# controller.net
KiCad netlist of a schematic drawn in EAGLE
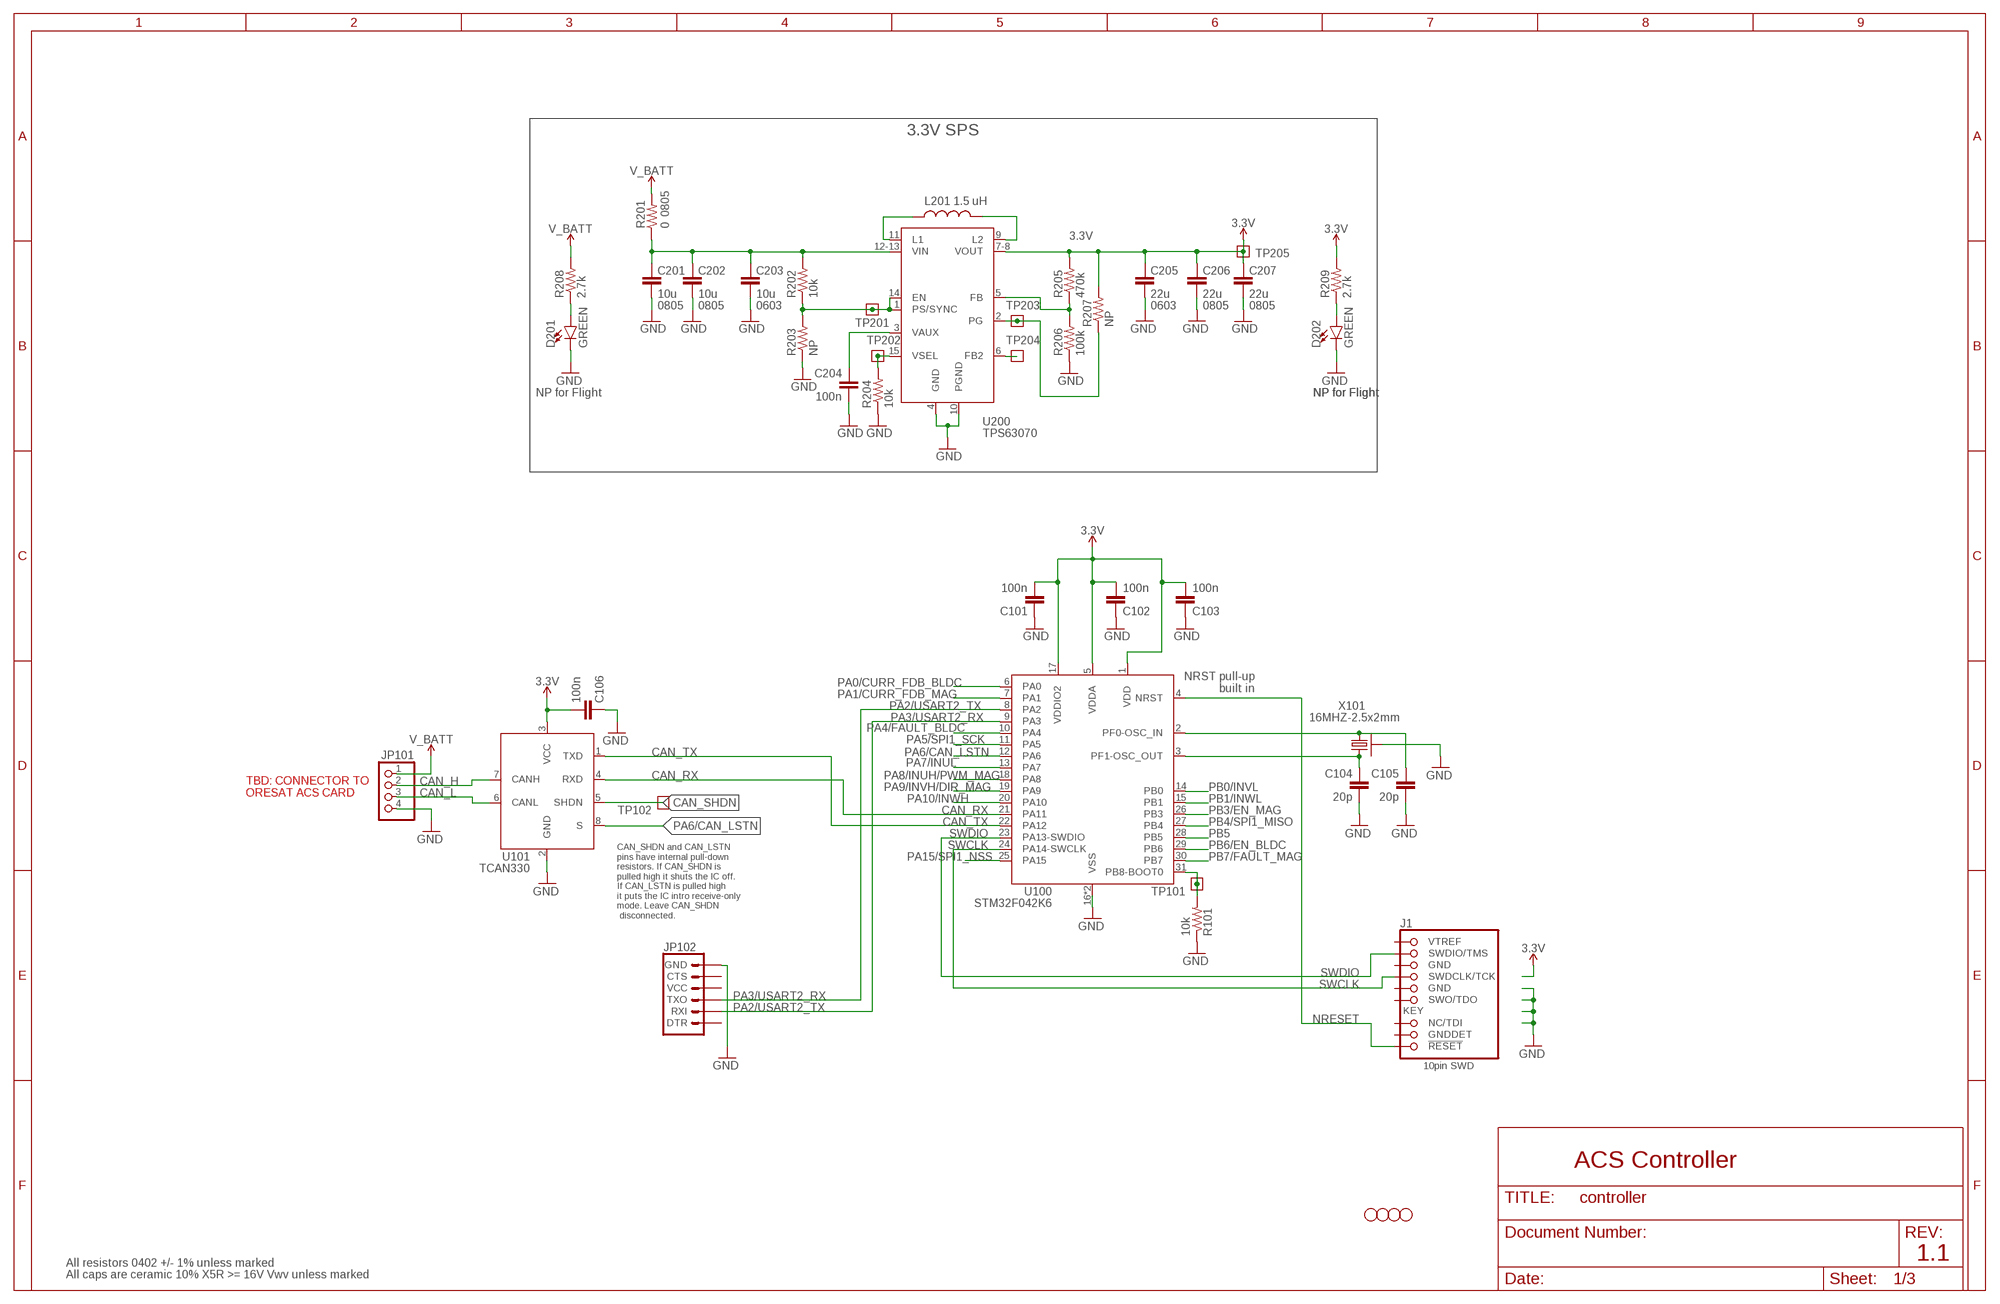
[diagram p0: schematic, sheet 1]
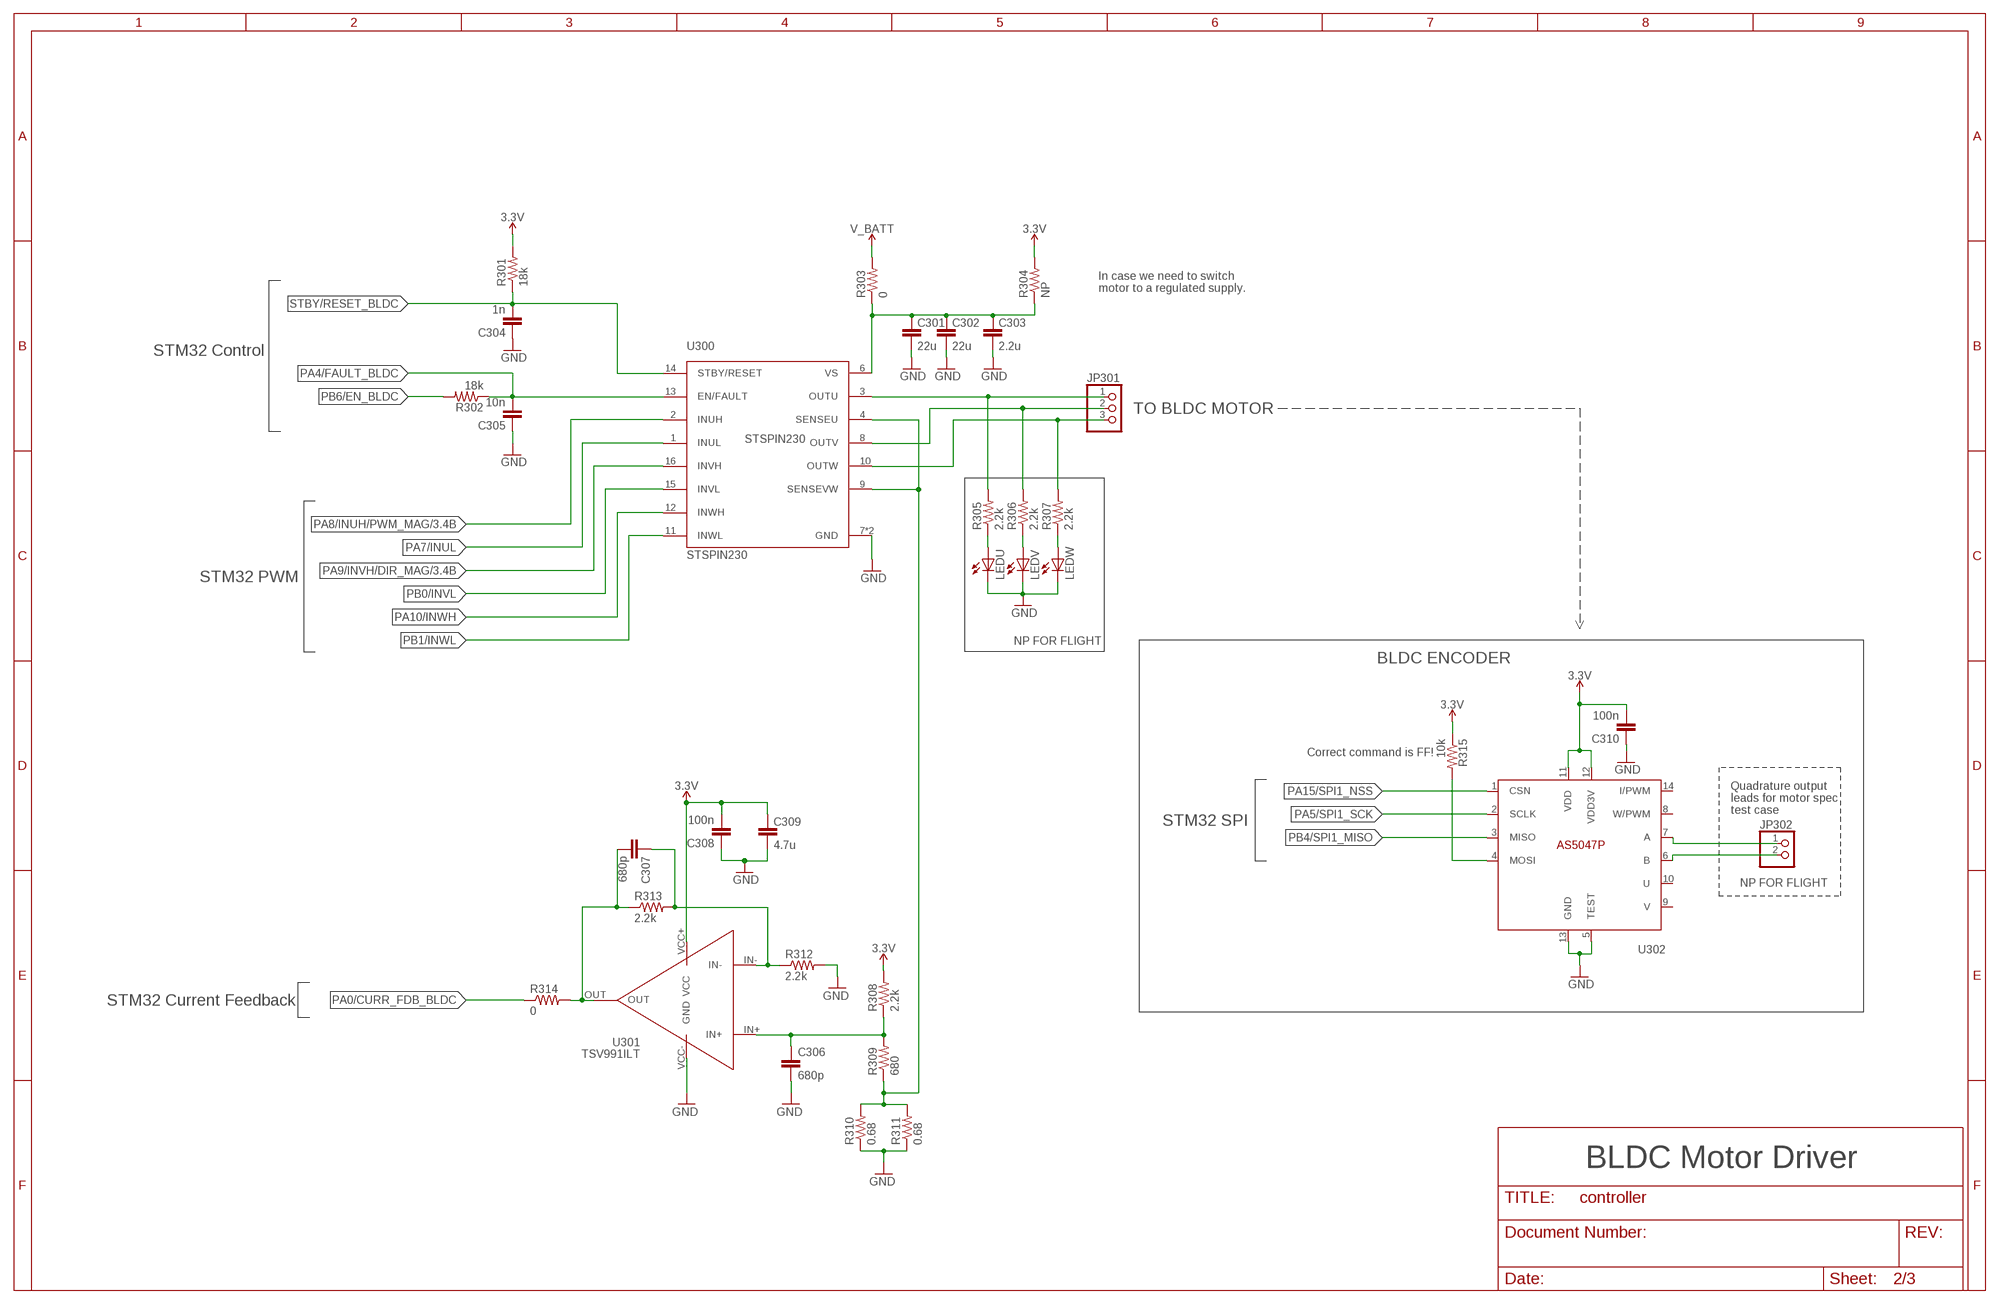
[diagram p1: schematic, sheet 2]
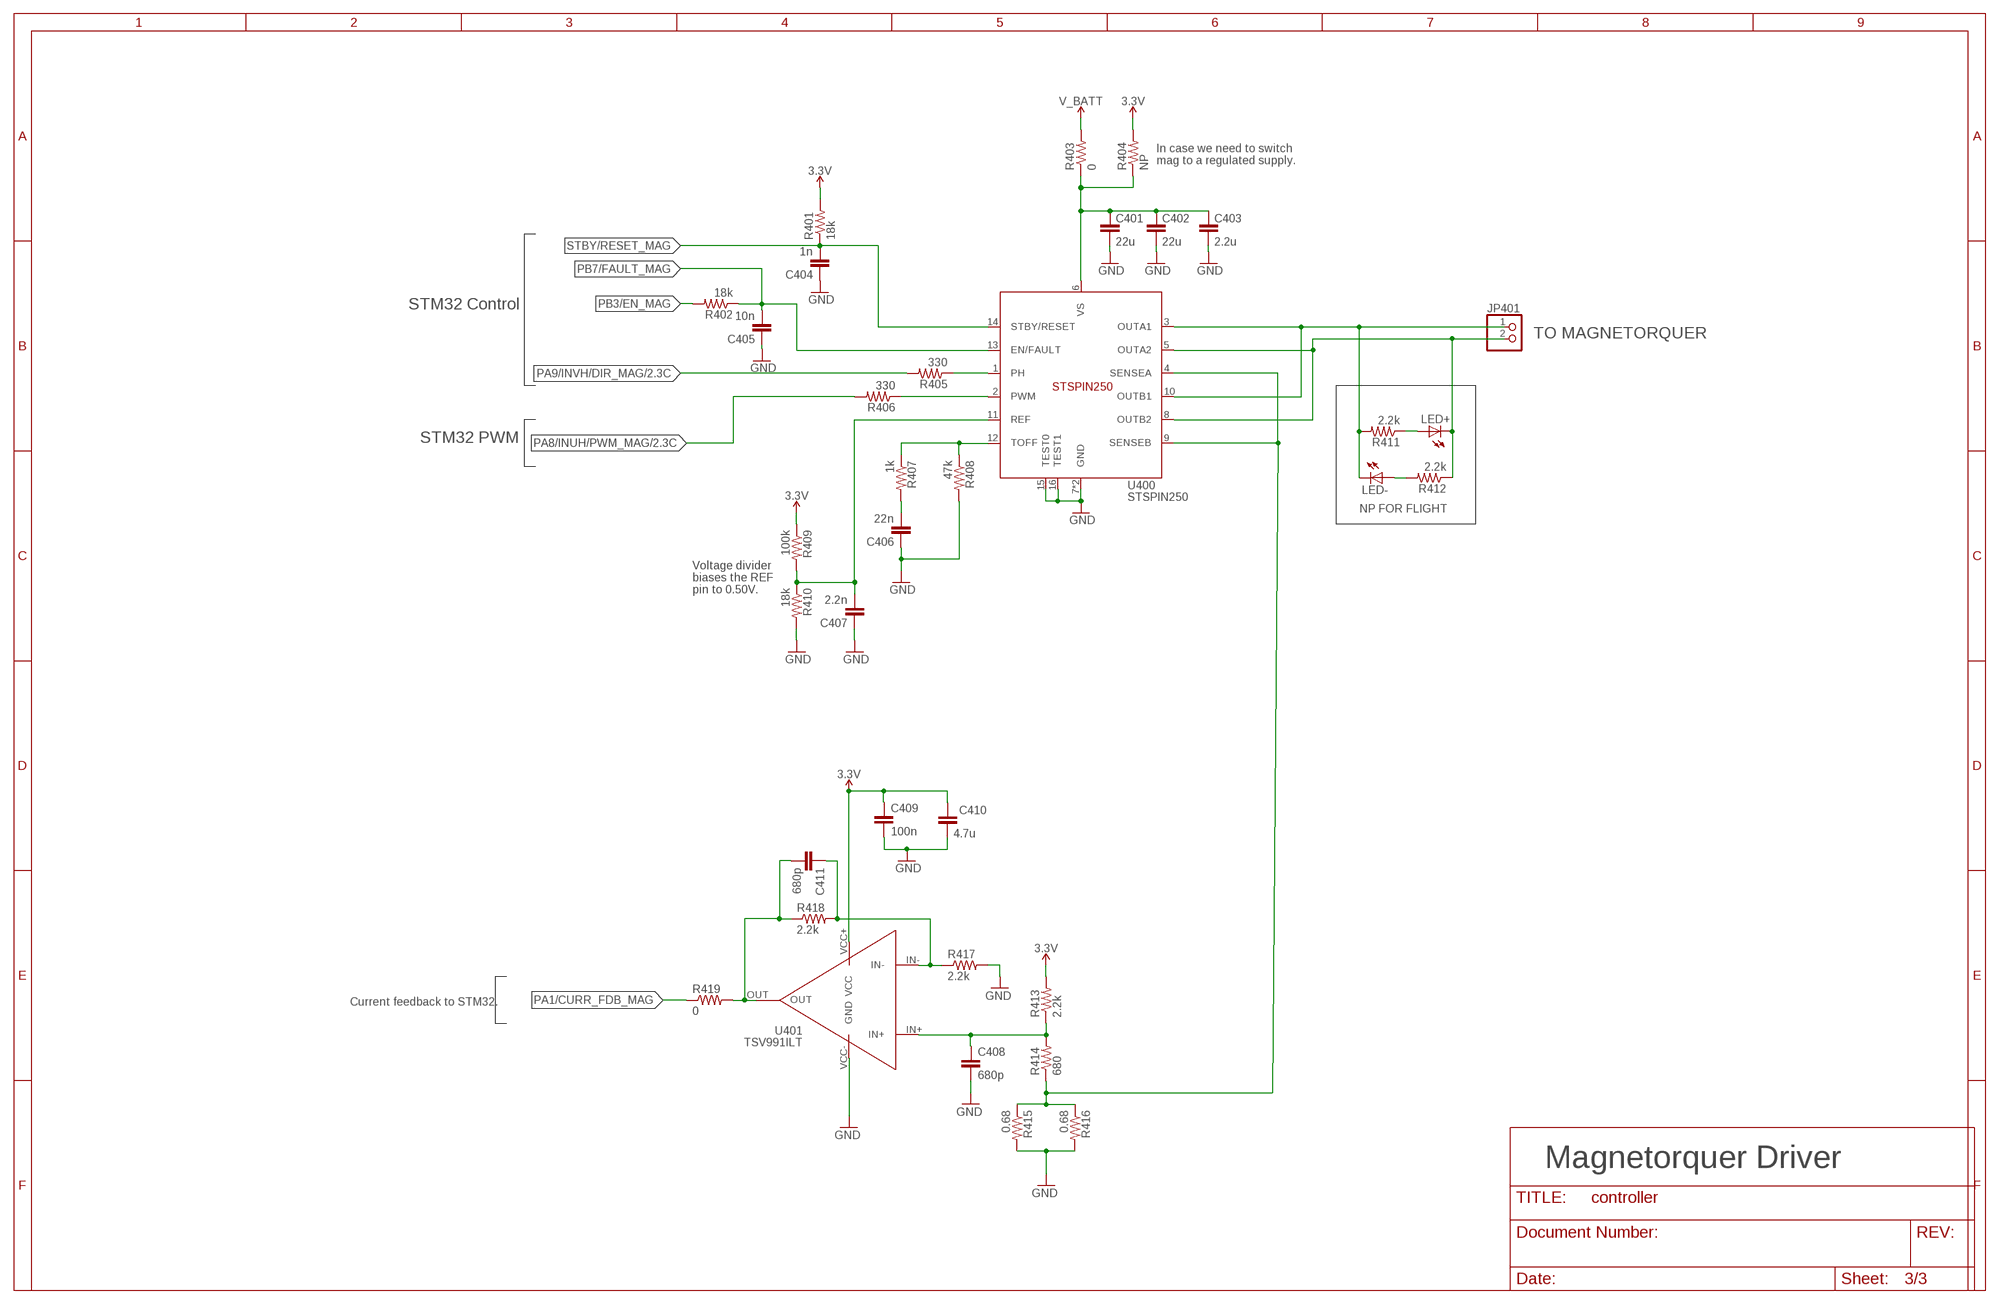
[diagram p2: schematic, sheet 3]

(export (version "E")
  (design (tool "Eeschema 10.0.6"))
  (components
    (comp (ref "C101")
      (value "100n")
      (footprint "eagle-import:.0402-B-NOSILK")
      (fields (field (name "MFR") "Samsung") (field (name "MPN") "CL05B104KO5NNNC"))
      (libsource (lib "eagle-import") (part "rcl_custom_C-EU0402-B-NOSILK"))
    )
    (comp (ref "C102")
      (value "100n")
      (footprint "eagle-import:.0402-B-NOSILK")
      (fields (field (name "MFR") "Samsung") (field (name "MPN") "CL05B104KO5NNNC"))
      (libsource (lib "eagle-import") (part "rcl_custom_C-EU0402-B-NOSILK"))
    )
    (comp (ref "C103")
      (value "100n")
      (footprint "eagle-import:.0402-B-NOSILK")
      (fields (field (name "MFR") "Samsung") (field (name "MPN") "CL05B104KO5NNNC"))
      (libsource (lib "eagle-import") (part "rcl_custom_C-EU0402-B-NOSILK"))
    )
    (comp (ref "C104")
      (value "20p")
      (footprint "eagle-import:.0402-B-NOSILK")
      (fields (field (name "MFR") "Samsung") (field (name "MPN") "CL05C200JB51PNC"))
      (libsource (lib "eagle-import") (part "rcl_custom_C-EU0402-B-NOSILK"))
    )
    (comp (ref "C105")
      (value "20p")
      (footprint "eagle-import:.0402-B-NOSILK")
      (fields (field (name "MFR") "Samsung") (field (name "MPN") "CL05C200JB51PNC"))
      (libsource (lib "eagle-import") (part "rcl_custom_C-EU0402-B-NOSILK"))
    )
    (comp (ref "C106")
      (value "100n")
      (footprint "eagle-import:.0402-B-NOSILK")
      (fields (field (name "MFR") "Samsung") (field (name "MPN") "CL05B104KO5NNNC"))
      (libsource (lib "eagle-import") (part "rcl_custom_C-EU0402-B-NOSILK"))
    )
    (comp (ref "C201")
      (value "10u")
      (footprint "eagle-import:.0805-B-NOSILK")
      (libsource (lib "eagle-import") (part "C-EU0805-B-NOSILK"))
    )
    (comp (ref "C202")
      (value "10u")
      (footprint "eagle-import:.0805-B-NOSILK")
      (libsource (lib "eagle-import") (part "C-EU0805-B-NOSILK"))
    )
    (comp (ref "C203")
      (value "10u")
      (footprint "eagle-import:.0603-B-NOSILK")
      (fields (field (name "MFR") "Samsung") (field (name "MPN") "CL05B104KO5NNNC"))
      (libsource (lib "eagle-import") (part "C-EU0603-B-NOSILK"))
    )
    (comp (ref "C204")
      (value "100n")
      (footprint "eagle-import:.0402-B-NOSILK")
      (fields (field (name "MFR") "Samsung") (field (name "MPN") "CL05B104KO5NNNC"))
      (libsource (lib "eagle-import") (part "rcl_custom_C-EU0402-B-NOSILK"))
    )
    (comp (ref "C205")
      (value "22u")
      (footprint "eagle-import:.0603-B-NOSILK")
      (fields (field (name "MFR") "Samsung") (field (name "MPN") "CL05B104KO5NNNC"))
      (libsource (lib "eagle-import") (part "C-EU0603-B-NOSILK"))
    )
    (comp (ref "C206")
      (value "22u")
      (footprint "eagle-import:.0805-B-NOSILK")
      (libsource (lib "eagle-import") (part "C-EU0805-B-NOSILK"))
    )
    (comp (ref "C207")
      (value "22u")
      (footprint "eagle-import:.0805-B-NOSILK")
      (libsource (lib "eagle-import") (part "C-EU0805-B-NOSILK"))
    )
    (comp (ref "D201")
      (value "GREEN")
      (footprint "eagle-import:LED-0603")
      (libsource (lib "eagle-import") (part "LED-GREEN0603"))
    )
    (comp (ref "D202")
      (value "GREEN")
      (footprint "eagle-import:LED-0603")
      (libsource (lib "eagle-import") (part "LED-GREEN0603"))
    )
    (comp (ref "H1")
      (value "STAND-OFFTIGHT")
      (footprint "eagle-import:STAND-OFF-TIGHT")
      (libsource (lib "eagle-import") (part "STAND-OFFTIGHT"))
    )
    (comp (ref "H2")
      (value "STAND-OFFTIGHT")
      (footprint "eagle-import:STAND-OFF-TIGHT")
      (libsource (lib "eagle-import") (part "STAND-OFFTIGHT"))
    )
    (comp (ref "H3")
      (value "STAND-OFFTIGHT")
      (footprint "eagle-import:STAND-OFF-TIGHT")
      (libsource (lib "eagle-import") (part "STAND-OFFTIGHT"))
    )
    (comp (ref "H4")
      (value "STAND-OFFTIGHT")
      (footprint "eagle-import:STAND-OFF-TIGHT")
      (libsource (lib "eagle-import") (part "STAND-OFFTIGHT"))
    )
    (comp (ref "J1")
      (value "1.27MM-SWD-CONNECTOR")
      (footprint "eagle-import:1.27MM_2X5")
      (libsource (lib "eagle-import") (part "1.27MM-SWD-CONNECTOR"))
    )
    (comp (ref "JP101")
      (value "PINHD-1X4")
      (footprint "eagle-import:1X04")
      (libsource (lib "eagle-import") (part "PINHD-1X4"))
    )
    (comp (ref "JP102")
      (value "6_PIN_SERIAL_TARGETSILK")
      (footprint "eagle-import:6_PIN_SERIAL_TARGET_SIDE_W_SILK")
      (libsource (lib "eagle-import") (part "6_PIN_SERIAL_TARGETSILK"))
    )
    (comp (ref "L201")
      (value "1.5 uH")
      (footprint "eagle-import:L-COILCRAFT-XFL4020")
      (fields (field (name "MFR") "Coilcraft") (field (name "MPN") "XFL4020-152ME"))
      (libsource (lib "eagle-import") (part "L-COILCRAFT-XFL4020"))
    )
    (comp (ref "R101")
      (value "10k")
      (footprint "eagle-import:.0402-B-NOSILK")
      (fields (field (name "MFR") "Samsung") (field (name "MPN") "RC1005F6653CS"))
      (libsource (lib "eagle-import") (part "rcl_custom_R-US_0402-B-NOSILK"))
    )
    (comp (ref "R201")
      (value "0")
      (footprint "eagle-import:.0805-B-NOSILK")
      (fields (field (name "MFR") "Rohm") (field (name "MPN") "MCR10EZPJ000"))
      (libsource (lib "eagle-import") (part "rcl_custom_R-US_0805-B-NOSILK"))
    )
    (comp (ref "R202")
      (value "10k")
      (footprint "eagle-import:.0402-B-NOSILK")
      (fields (field (name "MFR") "Samsung") (field (name "MPN") "RC1005F6653CS"))
      (libsource (lib "eagle-import") (part "rcl_custom_R-US_0402-B-NOSILK"))
    )
    (comp (ref "R203")
      (value "NP")
      (footprint "eagle-import:.0402-B-NOSILK")
      (fields (field (name "MFR") "Samsung") (field (name "MPN") "RC1005F6653CS"))
      (libsource (lib "eagle-import") (part "rcl_custom_R-US_0402-B-NOSILK"))
    )
    (comp (ref "R204")
      (value "10k")
      (footprint "eagle-import:.0402-B-NOSILK")
      (fields (field (name "MFR") "Samsung") (field (name "MPN") "RC1005F6653CS"))
      (libsource (lib "eagle-import") (part "rcl_custom_R-US_0402-B-NOSILK"))
    )
    (comp (ref "R205")
      (value "470k")
      (footprint "eagle-import:.0402-B-NOSILK")
      (fields (field (name "MFR") "Samsung") (field (name "MPN") "RC1005F6653CS"))
      (libsource (lib "eagle-import") (part "rcl_custom_R-US_0402-B-NOSILK"))
    )
    (comp (ref "R206")
      (value "100k")
      (footprint "eagle-import:.0402-B-NOSILK")
      (fields (field (name "MFR") "Samsung") (field (name "MPN") "RC1005F6653CS"))
      (libsource (lib "eagle-import") (part "rcl_custom_R-US_0402-B-NOSILK"))
    )
    (comp (ref "R207")
      (value "NP")
      (footprint "eagle-import:.0402-B-NOSILK")
      (fields (field (name "MFR") "Samsung") (field (name "MPN") "RC1005F6653CS"))
      (libsource (lib "eagle-import") (part "rcl_custom_R-US_0402-B-NOSILK"))
    )
    (comp (ref "R208")
      (value "2.7k")
      (footprint "eagle-import:.0402-B-NOSILK")
      (fields (field (name "MFR") "Samsung") (field (name "MPN") "RC1005F6653CS"))
      (libsource (lib "eagle-import") (part "rcl_custom_R-US_0402-B-NOSILK"))
    )
    (comp (ref "R209")
      (value "2.7k")
      (footprint "eagle-import:.0402-B-NOSILK")
      (fields (field (name "MFR") "Samsung") (field (name "MPN") "RC1005F6653CS"))
      (libsource (lib "eagle-import") (part "rcl_custom_R-US_0402-B-NOSILK"))
    )
    (comp (ref "TP101")
      (value "TEST-POINT")
      (footprint "eagle-import:2MM-TEST-POINT")
      (libsource (lib "eagle-import") (part "TEST-POINT"))
    )
    (comp (ref "TP102")
      (value "TEST-POINT")
      (footprint "eagle-import:2MM-TEST-POINT")
      (libsource (lib "eagle-import") (part "TEST-POINT"))
    )
    (comp (ref "TP201")
      (value "TEST-POINT")
      (footprint "eagle-import:2MM-TEST-POINT")
      (libsource (lib "eagle-import") (part "TEST-POINT"))
    )
    (comp (ref "TP202")
      (value "TEST-POINT")
      (footprint "eagle-import:2MM-TEST-POINT")
      (libsource (lib "eagle-import") (part "TEST-POINT"))
    )
    (comp (ref "TP203")
      (value "TEST-POINT")
      (footprint "eagle-import:2MM-TEST-POINT")
      (libsource (lib "eagle-import") (part "TEST-POINT"))
    )
    (comp (ref "TP204")
      (value "TEST-POINT")
      (footprint "eagle-import:2MM-TEST-POINT")
      (libsource (lib "eagle-import") (part "TEST-POINT"))
    )
    (comp (ref "TP205")
      (value "TEST-POINT")
      (footprint "eagle-import:2MM-TEST-POINT")
      (libsource (lib "eagle-import") (part "TEST-POINT"))
    )
    (comp (ref "U100")
      (value "STM32F042K6")
      (footprint "eagle-import:QFP32-7X7")
      (fields (field (name "MFR") "STMicroelectronics") (field (name "MPN") "STM32F042K6T7"))
      (libsource (lib "eagle-import") (part "STM32F042K6"))
    )
    (comp (ref "U101")
      (value "TCAN330")
      (footprint "eagle-import:SOT23-8_TI-DCN")
      (fields (field (name "MFR") "Texas Instruments") (field (name "MPN") "TCAN330GDCNT"))
      (libsource (lib "eagle-import") (part "TCAN330"))
    )
    (comp (ref "U200")
      (value "TPS63070")
      (footprint "eagle-import:TPS63070X")
      (libsource (lib "eagle-import") (part "TPS63070X"))
    )
    (comp (ref "X101")
      (value "16MHZ-2.5x2mm")
      (footprint "eagle-import:CRYSTAL_2.5X2")
      (fields (field (name "MFR") "ECS Inc.") (field (name "MPN") "ECS-160-10-36Q-ES-TR"))
      (libsource (lib "eagle-import") (part "CRYSTAL-WITH-GND"))
    )
    (comp (ref "C401")
      (value "22u")
      (footprint "eagle-import:.0603-B-NOSILK")
      (fields (field (name "MFR") "Samsung") (field (name "MPN") "CL05B104KO5NNNC"))
      (libsource (lib "eagle-import") (part "C-EU0603-B-NOSILK"))
    )
    (comp (ref "C402")
      (value "22u")
      (footprint "eagle-import:.0603-B-NOSILK")
      (fields (field (name "MFR") "Samsung") (field (name "MPN") "CL05B104KO5NNNC"))
      (libsource (lib "eagle-import") (part "C-EU0603-B-NOSILK"))
    )
    (comp (ref "C403")
      (value "2.2u")
      (footprint "eagle-import:.0603-B-NOSILK")
      (fields (field (name "MFR") "Samsung") (field (name "MPN") "CL05B104KO5NNNC"))
      (libsource (lib "eagle-import") (part "C-EU0603-B-NOSILK"))
    )
    (comp (ref "C404")
      (value "1n")
      (footprint "eagle-import:.0402-B-NOSILK")
      (fields (field (name "MFR") "Samsung") (field (name "MPN") "CL05B104KO5NNNC"))
      (libsource (lib "eagle-import") (part "rcl_custom_C-EU0402-B-NOSILK"))
    )
    (comp (ref "C405")
      (value "10n")
      (footprint "eagle-import:.0402-B-NOSILK")
      (fields (field (name "MFR") "Samsung") (field (name "MPN") "CL05B104KO5NNNC"))
      (libsource (lib "eagle-import") (part "rcl_custom_C-EU0402-B-NOSILK"))
    )
    (comp (ref "C406")
      (value "22n")
      (footprint "eagle-import:.0402-B-NOSILK")
      (fields (field (name "MFR") "Samsung") (field (name "MPN") "CL05B104KO5NNNC"))
      (libsource (lib "eagle-import") (part "rcl_custom_C-EU0402-B-NOSILK"))
    )
    (comp (ref "C407")
      (value "2.2n")
      (footprint "eagle-import:.0402-B-NOSILK")
      (fields (field (name "MFR") "Samsung") (field (name "MPN") "CL05B104KO5NNNC"))
      (libsource (lib "eagle-import") (part "rcl_custom_C-EU0402-B-NOSILK"))
    )
    (comp (ref "C408")
      (value "680p")
      (footprint "eagle-import:.0402-B-NOSILK")
      (fields (field (name "MFR") "Samsung") (field (name "MPN") "CL05B104KO5NNNC"))
      (libsource (lib "eagle-import") (part "rcl_custom_C-EU0402-B-NOSILK"))
    )
    (comp (ref "C409")
      (value "100n")
      (footprint "eagle-import:.0402-B-NOSILK")
      (fields (field (name "MFR") "Samsung") (field (name "MPN") "CL05B104KO5NNNC"))
      (libsource (lib "eagle-import") (part "rcl_custom_C-EU0402-B-NOSILK"))
    )
    (comp (ref "C410")
      (value "4.7u")
      (footprint "eagle-import:.0603-B-NOSILK")
      (fields (field (name "MFR") "Samsung") (field (name "MPN") "CL05B104KO5NNNC"))
      (libsource (lib "eagle-import") (part "C-EU0603-B-NOSILK"))
    )
    (comp (ref "C411")
      (value "680p")
      (footprint "eagle-import:.0402-B-NOSILK")
      (fields (field (name "MFR") "Samsung") (field (name "MPN") "CL05B104KO5NNNC"))
      (libsource (lib "eagle-import") (part "rcl_custom_C-EU0402-B-NOSILK"))
    )
    (comp (ref "JP401")
      (value "PINHD-1X2")
      (footprint "eagle-import:1X02")
      (libsource (lib "eagle-import") (part "PINHD-1X2"))
    )
    (comp (ref "LED+")
      (value "LEDCHIP-LED0603")
      (footprint "eagle-import:CHIP-LED0603")
      (libsource (lib "eagle-import") (part "LEDCHIP-LED0603"))
    )
    (comp (ref "LED-")
      (value "LEDCHIP-LED0603")
      (footprint "eagle-import:CHIP-LED0603")
      (libsource (lib "eagle-import") (part "LEDCHIP-LED0603"))
    )
    (comp (ref "R401")
      (value "18k")
      (footprint "eagle-import:.0402-B-NOSILK")
      (fields (field (name "MFR") "Samsung") (field (name "MPN") "RC1005F6653CS"))
      (libsource (lib "eagle-import") (part "rcl_custom_R-US_0402-B-NOSILK"))
    )
    (comp (ref "R402")
      (value "18k")
      (footprint "eagle-import:.0402-B-NOSILK")
      (fields (field (name "MFR") "Samsung") (field (name "MPN") "RC1005F6653CS"))
      (libsource (lib "eagle-import") (part "rcl_custom_R-US_0402-B-NOSILK"))
    )
    (comp (ref "R403")
      (value "0")
      (footprint "eagle-import:.0805-B-NOSILK")
      (libsource (lib "eagle-import") (part "R-US_0805-B-NOSILK"))
    )
    (comp (ref "R404")
      (value "NP")
      (footprint "eagle-import:.0805-B-NOSILK")
      (libsource (lib "eagle-import") (part "R-US_0805-B-NOSILK"))
    )
    (comp (ref "R405")
      (value "330")
      (footprint "eagle-import:.0402-B-NOSILK")
      (fields (field (name "MFR") "Samsung") (field (name "MPN") "RC1005F6653CS"))
      (libsource (lib "eagle-import") (part "rcl_custom_R-US_0402-B-NOSILK"))
    )
    (comp (ref "R406")
      (value "330")
      (footprint "eagle-import:.0402-B-NOSILK")
      (fields (field (name "MFR") "Samsung") (field (name "MPN") "RC1005F6653CS"))
      (libsource (lib "eagle-import") (part "rcl_custom_R-US_0402-B-NOSILK"))
    )
    (comp (ref "R407")
      (value "1k")
      (footprint "eagle-import:.0402-B-NOSILK")
      (fields (field (name "MFR") "Samsung") (field (name "MPN") "RC1005F6653CS"))
      (libsource (lib "eagle-import") (part "rcl_custom_R-US_0402-B-NOSILK"))
    )
    (comp (ref "R408")
      (value "47k")
      (footprint "eagle-import:.0402-B-NOSILK")
      (fields (field (name "MFR") "Samsung") (field (name "MPN") "RC1005F6653CS"))
      (libsource (lib "eagle-import") (part "rcl_custom_R-US_0402-B-NOSILK"))
    )
    (comp (ref "R409")
      (value "100k")
      (footprint "eagle-import:.0402-B-NOSILK")
      (fields (field (name "MFR") "Samsung") (field (name "MPN") "RC1005F6653CS"))
      (libsource (lib "eagle-import") (part "rcl_custom_R-US_0402-B-NOSILK"))
    )
    (comp (ref "R410")
      (value "18k")
      (footprint "eagle-import:.0402-B-NOSILK")
      (fields (field (name "MFR") "Samsung") (field (name "MPN") "RC1005F6653CS"))
      (libsource (lib "eagle-import") (part "rcl_custom_R-US_0402-B-NOSILK"))
    )
    (comp (ref "R411")
      (value "2.2k")
      (footprint "eagle-import:.0805-B-NOSILK")
      (libsource (lib "eagle-import") (part "R-US_0805-B-NOSILK"))
    )
    (comp (ref "R412")
      (value "2.2k")
      (footprint "eagle-import:.0805-B-NOSILK")
      (libsource (lib "eagle-import") (part "R-US_0805-B-NOSILK"))
    )
    (comp (ref "R413")
      (value "2.2k")
      (footprint "eagle-import:.0402-B-NOSILK")
      (fields (field (name "MFR") "Samsung") (field (name "MPN") "RC1005F6653CS"))
      (libsource (lib "eagle-import") (part "rcl_custom_R-US_0402-B-NOSILK"))
    )
    (comp (ref "R414")
      (value "680")
      (footprint "eagle-import:.0402-B-NOSILK")
      (fields (field (name "MFR") "Samsung") (field (name "MPN") "RC1005F6653CS"))
      (libsource (lib "eagle-import") (part "rcl_custom_R-US_0402-B-NOSILK"))
    )
    (comp (ref "R415")
      (value "0.68")
      (footprint "eagle-import:.0805-B-NOSILK")
      (libsource (lib "eagle-import") (part "R-US_0805-B-NOSILK"))
    )
    (comp (ref "R416")
      (value "0.68")
      (footprint "eagle-import:.0805-B-NOSILK")
      (libsource (lib "eagle-import") (part "R-US_0805-B-NOSILK"))
    )
    (comp (ref "R417")
      (value "2.2k")
      (footprint "eagle-import:.0402-B-NOSILK")
      (fields (field (name "MFR") "Samsung") (field (name "MPN") "RC1005F6653CS"))
      (libsource (lib "eagle-import") (part "rcl_custom_R-US_0402-B-NOSILK"))
    )
    (comp (ref "R418")
      (value "2.2k")
      (footprint "eagle-import:.0402-B-NOSILK")
      (fields (field (name "MFR") "Samsung") (field (name "MPN") "RC1005F6653CS"))
      (libsource (lib "eagle-import") (part "rcl_custom_R-US_0402-B-NOSILK"))
    )
    (comp (ref "R419")
      (value "0")
      (footprint "eagle-import:.0402-B-NOSILK")
      (fields (field (name "MFR") "Samsung") (field (name "MPN") "RC1005F6653CS"))
      (libsource (lib "eagle-import") (part "rcl_custom_R-US_0402-B-NOSILK"))
    )
    (comp (ref "U400")
      (value "STSPIN250")
      (footprint "eagle-import:VFQPN")
      (libsource (lib "eagle-import") (part "STSPIN250"))
    )
    (comp (ref "U401")
      (value "TSV991ILT")
      (footprint "eagle-import:SOT23-5")
      (libsource (lib "eagle-import") (part "TSV991ILT"))
    )
    (comp (ref "C301")
      (value "22u")
      (footprint "eagle-import:.0603-B-NOSILK")
      (fields (field (name "MFR") "Samsung") (field (name "MPN") "CL05B104KO5NNNC"))
      (libsource (lib "eagle-import") (part "C-EU0603-B-NOSILK"))
    )
    (comp (ref "C302")
      (value "22u")
      (footprint "eagle-import:.0603-B-NOSILK")
      (fields (field (name "MFR") "Samsung") (field (name "MPN") "CL05B104KO5NNNC"))
      (libsource (lib "eagle-import") (part "C-EU0603-B-NOSILK"))
    )
    (comp (ref "C303")
      (value "2.2u")
      (footprint "eagle-import:.0603-B-NOSILK")
      (fields (field (name "MFR") "Samsung") (field (name "MPN") "CL05B104KO5NNNC"))
      (libsource (lib "eagle-import") (part "C-EU0603-B-NOSILK"))
    )
    (comp (ref "C304")
      (value "1n")
      (footprint "eagle-import:.0402-B-NOSILK")
      (fields (field (name "MFR") "Samsung") (field (name "MPN") "CL05B104KO5NNNC"))
      (libsource (lib "eagle-import") (part "rcl_custom_C-EU0402-B-NOSILK"))
    )
    (comp (ref "C305")
      (value "10n")
      (footprint "eagle-import:.0402-B-NOSILK")
      (fields (field (name "MFR") "Samsung") (field (name "MPN") "CL05B104KO5NNNC"))
      (libsource (lib "eagle-import") (part "rcl_custom_C-EU0402-B-NOSILK"))
    )
    (comp (ref "C306")
      (value "680p")
      (footprint "eagle-import:.0402-B-NOSILK")
      (fields (field (name "MFR") "Samsung") (field (name "MPN") "CL05B104KO5NNNC"))
      (libsource (lib "eagle-import") (part "rcl_custom_C-EU0402-B-NOSILK"))
    )
    (comp (ref "C307")
      (value "680p")
      (footprint "eagle-import:.0402-B-NOSILK")
      (fields (field (name "MFR") "Samsung") (field (name "MPN") "CL05B104KO5NNNC"))
      (libsource (lib "eagle-import") (part "rcl_custom_C-EU0402-B-NOSILK"))
    )
    (comp (ref "C308")
      (value "100n")
      (footprint "eagle-import:.0402-B-NOSILK")
      (fields (field (name "MFR") "Samsung") (field (name "MPN") "CL05B104KO5NNNC"))
      (libsource (lib "eagle-import") (part "rcl_custom_C-EU0402-B-NOSILK"))
    )
    (comp (ref "C309")
      (value "4.7u")
      (footprint "eagle-import:.0603-B-NOSILK")
      (fields (field (name "MFR") "Samsung") (field (name "MPN") "CL05B104KO5NNNC"))
      (libsource (lib "eagle-import") (part "C-EU0603-B-NOSILK"))
    )
    (comp (ref "C310")
      (value "100n")
      (footprint "eagle-import:.0402-B-NOSILK")
      (fields (field (name "MFR") "Samsung") (field (name "MPN") "CL05B104KO5NNNC"))
      (libsource (lib "eagle-import") (part "rcl_custom_C-EU0402-B-NOSILK"))
    )
    (comp (ref "JP301")
      (value "PINHD-1X3")
      (footprint "eagle-import:1X03")
      (libsource (lib "eagle-import") (part "PINHD-1X3"))
    )
    (comp (ref "JP302")
      (value "PINHD-1X2")
      (footprint "eagle-import:1X02")
      (libsource (lib "eagle-import") (part "PINHD-1X2"))
    )
    (comp (ref "LEDU")
      (value "LEDCHIP-LED0603")
      (footprint "eagle-import:CHIP-LED0603")
      (libsource (lib "eagle-import") (part "LEDCHIP-LED0603"))
    )
    (comp (ref "LEDV")
      (value "LEDCHIP-LED0603")
      (footprint "eagle-import:CHIP-LED0603")
      (libsource (lib "eagle-import") (part "LEDCHIP-LED0603"))
    )
    (comp (ref "LEDW")
      (value "LEDCHIP-LED0603")
      (footprint "eagle-import:CHIP-LED0603")
      (libsource (lib "eagle-import") (part "LEDCHIP-LED0603"))
    )
    (comp (ref "R301")
      (value "18k")
      (footprint "eagle-import:.0402-B-NOSILK")
      (fields (field (name "MFR") "Samsung") (field (name "MPN") "RC1005F6653CS"))
      (libsource (lib "eagle-import") (part "rcl_custom_R-US_0402-B-NOSILK"))
    )
    (comp (ref "R302")
      (value "18k")
      (footprint "eagle-import:.0402-B-NOSILK")
      (fields (field (name "MFR") "Samsung") (field (name "MPN") "RC1005F6653CS"))
      (libsource (lib "eagle-import") (part "rcl_custom_R-US_0402-B-NOSILK"))
    )
    (comp (ref "R303")
      (value "0")
      (footprint "eagle-import:.0805-B-NOSILK")
      (libsource (lib "eagle-import") (part "R-US_0805-B-NOSILK"))
    )
    (comp (ref "R304")
      (value "NP")
      (footprint "eagle-import:.0805-B-NOSILK")
      (libsource (lib "eagle-import") (part "R-US_0805-B-NOSILK"))
    )
    (comp (ref "R305")
      (value "2.2k")
      (footprint "eagle-import:.0805-B-NOSILK")
      (libsource (lib "eagle-import") (part "R-US_0805-B-NOSILK"))
    )
    (comp (ref "R306")
      (value "2.2k")
      (footprint "eagle-import:.0805-B-NOSILK")
      (libsource (lib "eagle-import") (part "R-US_0805-B-NOSILK"))
    )
    (comp (ref "R307")
      (value "2.2k")
      (footprint "eagle-import:.0805-B-NOSILK")
      (libsource (lib "eagle-import") (part "R-US_0805-B-NOSILK"))
    )
    (comp (ref "R308")
      (value "2.2k")
      (footprint "eagle-import:.0402-B-NOSILK")
      (fields (field (name "MFR") "Samsung") (field (name "MPN") "RC1005F6653CS"))
      (libsource (lib "eagle-import") (part "rcl_custom_R-US_0402-B-NOSILK"))
    )
    (comp (ref "R309")
      (value "680")
      (footprint "eagle-import:.0402-B-NOSILK")
      (fields (field (name "MFR") "Samsung") (field (name "MPN") "RC1005F6653CS"))
      (libsource (lib "eagle-import") (part "rcl_custom_R-US_0402-B-NOSILK"))
    )
    (comp (ref "R310")
      (value "0.68")
      (footprint "eagle-import:.0805-B-NOSILK")
      (libsource (lib "eagle-import") (part "R-US_0805-B-NOSILK"))
    )
    (comp (ref "R311")
      (value "0.68")
      (footprint "eagle-import:.0805-B-NOSILK")
      (libsource (lib "eagle-import") (part "R-US_0805-B-NOSILK"))
    )
    (comp (ref "R312")
      (value "2.2k")
      (footprint "eagle-import:.0402-B-NOSILK")
      (fields (field (name "MFR") "Samsung") (field (name "MPN") "RC1005F6653CS"))
      (libsource (lib "eagle-import") (part "rcl_custom_R-US_0402-B-NOSILK"))
    )
    (comp (ref "R313")
      (value "2.2k")
      (footprint "eagle-import:.0402-B-NOSILK")
      (fields (field (name "MFR") "Samsung") (field (name "MPN") "RC1005F6653CS"))
      (libsource (lib "eagle-import") (part "rcl_custom_R-US_0402-B-NOSILK"))
    )
    (comp (ref "R314")
      (value "0")
      (footprint "eagle-import:.0402-B-NOSILK")
      (fields (field (name "MFR") "Samsung") (field (name "MPN") "RC1005F6653CS"))
      (libsource (lib "eagle-import") (part "rcl_custom_R-US_0402-B-NOSILK"))
    )
    (comp (ref "R315")
      (value "10k")
      (footprint "eagle-import:.0402-B-NOSILK")
      (fields (field (name "MFR") "Samsung") (field (name "MPN") "RC1005F6653CS"))
      (libsource (lib "eagle-import") (part "rcl_custom_R-US_0402-B-NOSILK"))
    )
    (comp (ref "U300")
      (value "STSPIN230")
      (footprint "eagle-import:VFQFPN")
      (libsource (lib "eagle-import") (part "STSPIN230"))
    )
    (comp (ref "U301")
      (value "TSV991ILT")
      (footprint "eagle-import:SOT23-5")
      (libsource (lib "eagle-import") (part "TSV991ILT"))
    )
    (comp (ref "U302")
      (value "AS5047P")
      (footprint "eagle-import:TSSOP14")
      (libsource (lib "eagle-import") (part "AS5047P"))
    )
  )
  (nets
    (net (code "1") (name "3.3V") (class "Default")
      (node (ref "C101") (pin "2") (pinfunction "2_2") (pintype "passive"))
      (node (ref "C102") (pin "2") (pinfunction "2_2") (pintype "passive"))
      (node (ref "C103") (pin "2") (pinfunction "2_2") (pintype "passive"))
      (node (ref "C106") (pin "2") (pinfunction "2_2") (pintype "passive"))
      (node (ref "C205") (pin "1") (pinfunction "1_1") (pintype "passive"))
      (node (ref "C206") (pin "1") (pinfunction "1_1") (pintype "passive"))
      (node (ref "C207") (pin "1") (pinfunction "1_1") (pintype "passive"))
      (node (ref "C308") (pin "2") (pinfunction "2_2") (pintype "passive"))
      (node (ref "C309") (pin "1") (pinfunction "1_1") (pintype "passive"))
      (node (ref "C310") (pin "2") (pinfunction "2_2") (pintype "passive"))
      (node (ref "C409") (pin "1") (pinfunction "1_1") (pintype "passive"))
      (node (ref "C410") (pin "1") (pinfunction "1_1") (pintype "passive"))
      (node (ref "R205") (pin "2") (pinfunction "2_2") (pintype "passive"))
      (node (ref "R207") (pin "2") (pinfunction "2_2") (pintype "passive"))
      (node (ref "R209") (pin "2") (pinfunction "2_2") (pintype "passive"))
      (node (ref "R301") (pin "2") (pinfunction "2_2") (pintype "passive"))
      (node (ref "R304") (pin "2") (pinfunction "2_2") (pintype "passive"))
      (node (ref "R308") (pin "2") (pinfunction "2_2") (pintype "passive"))
      (node (ref "R315") (pin "1") (pinfunction "1_1") (pintype "passive"))
      (node (ref "R401") (pin "2") (pinfunction "2_2") (pintype "passive"))
      (node (ref "R404") (pin "2") (pinfunction "2_2") (pintype "passive"))
      (node (ref "R409") (pin "1") (pinfunction "1_1") (pintype "passive"))
      (node (ref "R413") (pin "2") (pinfunction "2_2") (pintype "passive"))
      (node (ref "TP205") (pin "1") (pinfunction "1_1") (pintype "passive"))
      (node (ref "U100") (pin "1") (pinfunction "VDD_1") (pintype "power_in"))
      (node (ref "U100") (pin "17") (pinfunction "VDDIO2_17") (pintype "power_in"))
      (node (ref "U100") (pin "5") (pinfunction "VDDA_5") (pintype "power_in"))
      (node (ref "U101") (pin "3") (pinfunction "VCC_3") (pintype "power_in"))
      (node (ref "U200") (pin "7-8") (pinfunction "VOUT_7-8") (pintype "power_in"))
      (node (ref "U301") (pin "VCC+") (pinfunction "VCC_VCC+") (pintype "bidirectional"))
      (node (ref "U302") (pin "11") (pinfunction "VDD_11") (pintype "power_in"))
      (node (ref "U302") (pin "12") (pinfunction "VDD3V_12") (pintype "power_in"))
      (node (ref "U401") (pin "VCC+") (pinfunction "VCC_VCC+") (pintype "bidirectional"))
    )
    (net (code "2") (name "CAN_H") (class "Default")
      (node (ref "JP101") (pin "2") (pinfunction "2_2") (pintype "passive"))
      (node (ref "U101") (pin "7") (pinfunction "CANH_7") (pintype "bidirectional"))
    )
    (net (code "3") (name "CAN_L") (class "Default")
      (node (ref "JP101") (pin "3") (pinfunction "3_3") (pintype "passive"))
      (node (ref "U101") (pin "6") (pinfunction "CANL_6") (pintype "bidirectional"))
    )
    (net (code "4") (name "CAN_RX") (class "Default")
      (node (ref "U100") (pin "21") (pinfunction "PA11_21") (pintype "bidirectional"))
      (node (ref "U101") (pin "4") (pinfunction "RXD_4") (pintype "output"))
    )
    (net (code "5") (name "CAN_SHDN") (class "Default")
      (node (ref "TP102") (pin "1") (pinfunction "1_1") (pintype "passive"))
      (node (ref "U101") (pin "5") (pinfunction "SHDN_5") (pintype "input"))
    )
    (net (code "6") (name "CAN_TX") (class "Default")
      (node (ref "U100") (pin "22") (pinfunction "PA12_22") (pintype "bidirectional"))
      (node (ref "U101") (pin "1") (pinfunction "TXD_1") (pintype "input"))
    )
    (net (code "7") (name "GND") (class "Default")
      (node (ref "C101") (pin "1") (pinfunction "1_1") (pintype "passive"))
      (node (ref "C102") (pin "1") (pinfunction "1_1") (pintype "passive"))
      (node (ref "C103") (pin "1") (pinfunction "1_1") (pintype "passive"))
      (node (ref "C104") (pin "2") (pinfunction "2_2") (pintype "passive"))
      (node (ref "C105") (pin "2") (pinfunction "2_2") (pintype "passive"))
      (node (ref "C106") (pin "1") (pinfunction "1_1") (pintype "passive"))
      (node (ref "C201") (pin "2") (pinfunction "2_2") (pintype "passive"))
      (node (ref "C202") (pin "2") (pinfunction "2_2") (pintype "passive"))
      (node (ref "C203") (pin "2") (pinfunction "2_2") (pintype "passive"))
      (node (ref "C204") (pin "2") (pinfunction "2_2") (pintype "passive"))
      (node (ref "C205") (pin "2") (pinfunction "2_2") (pintype "passive"))
      (node (ref "C206") (pin "2") (pinfunction "2_2") (pintype "passive"))
      (node (ref "C207") (pin "2") (pinfunction "2_2") (pintype "passive"))
      (node (ref "C301") (pin "2") (pinfunction "2_2") (pintype "passive"))
      (node (ref "C302") (pin "2") (pinfunction "2_2") (pintype "passive"))
      (node (ref "C303") (pin "2") (pinfunction "2_2") (pintype "passive"))
      (node (ref "C304") (pin "1") (pinfunction "1_1") (pintype "passive"))
      (node (ref "C305") (pin "1") (pinfunction "1_1") (pintype "passive"))
      (node (ref "C306") (pin "2") (pinfunction "2_2") (pintype "passive"))
      (node (ref "C308") (pin "1") (pinfunction "1_1") (pintype "passive"))
      (node (ref "C309") (pin "2") (pinfunction "2_2") (pintype "passive"))
      (node (ref "C310") (pin "1") (pinfunction "1_1") (pintype "passive"))
      (node (ref "C401") (pin "2") (pinfunction "2_2") (pintype "passive"))
      (node (ref "C402") (pin "2") (pinfunction "2_2") (pintype "passive"))
      (node (ref "C403") (pin "2") (pinfunction "2_2") (pintype "passive"))
      (node (ref "C404") (pin "1") (pinfunction "1_1") (pintype "passive"))
      (node (ref "C405") (pin "1") (pinfunction "1_1") (pintype "passive"))
      (node (ref "C406") (pin "1") (pinfunction "1_1") (pintype "passive"))
      (node (ref "C407") (pin "1") (pinfunction "1_1") (pintype "passive"))
      (node (ref "C408") (pin "2") (pinfunction "2_2") (pintype "passive"))
      (node (ref "C409") (pin "2") (pinfunction "2_2") (pintype "passive"))
      (node (ref "C410") (pin "2") (pinfunction "2_2") (pintype "passive"))
      (node (ref "D201") (pin "C") (pinfunction "C_C") (pintype "passive"))
      (node (ref "D202") (pin "C") (pinfunction "C_C") (pintype "passive"))
      (node (ref "JP101") (pin "4") (pinfunction "4_4") (pintype "passive"))
      (node (ref "JP102") (pin "P$6") (pinfunction "GND_P$6") (pintype "passive"))
      (node (ref "LEDU") (pin "C") (pinfunction "C_C") (pintype "passive"))
      (node (ref "LEDV") (pin "C") (pinfunction "C_C") (pintype "passive"))
      (node (ref "LEDW") (pin "C") (pinfunction "C_C") (pintype "passive"))
      (node (ref "R101") (pin "1") (pinfunction "1_1") (pintype "passive"))
      (node (ref "R203") (pin "1") (pinfunction "1_1") (pintype "passive"))
      (node (ref "R204") (pin "1") (pinfunction "1_1") (pintype "passive"))
      (node (ref "R206") (pin "1") (pinfunction "1_1") (pintype "passive"))
      (node (ref "R310") (pin "1") (pinfunction "1_1") (pintype "passive"))
      (node (ref "R311") (pin "1") (pinfunction "1_1") (pintype "passive"))
      (node (ref "R312") (pin "2") (pinfunction "2_2") (pintype "passive"))
      (node (ref "R408") (pin "2") (pinfunction "2_2") (pintype "passive"))
      (node (ref "R410") (pin "2") (pinfunction "2_2") (pintype "passive"))
      (node (ref "R415") (pin "2") (pinfunction "2_2") (pintype "passive"))
      (node (ref "R416") (pin "2") (pinfunction "2_2") (pintype "passive"))
      (node (ref "R417") (pin "2") (pinfunction "2_2") (pintype "passive"))
      (node (ref "U100") (pin "16") (pinfunction "VSS_16") (pintype "power_in"))
      (node (ref "U100") (pin "32") (pinfunction "VSS_32") (pintype "power_in"))
      (node (ref "U101") (pin "2") (pinfunction "GND_2") (pintype "power_in"))
      (node (ref "U200") (pin "10") (pinfunction "PGND_10") (pintype "power_in"))
      (node (ref "U200") (pin "4") (pinfunction "GND_4") (pintype "power_in"))
      (node (ref "U300") (pin "7") (pinfunction "GND_7") (pintype "power_in"))
      (node (ref "U300") (pin "EPAD") (pinfunction "GND_EPAD") (pintype "power_in"))
      (node (ref "U301") (pin "VCC-") (pinfunction "GND_VCC-") (pintype "bidirectional"))
      (node (ref "U302") (pin "13") (pinfunction "GND_13") (pintype "power_in"))
      (node (ref "U302") (pin "5") (pinfunction "TEST_5") (pintype "power_in"))
      (node (ref "U400") (pin "15") (pinfunction "TEST0_15") (pintype "bidirectional"))
      (node (ref "U400") (pin "16") (pinfunction "TEST1_16") (pintype "bidirectional"))
      (node (ref "U400") (pin "7") (pinfunction "GND_7") (pintype "power_in"))
      (node (ref "U400") (pin "EPAD") (pinfunction "GND_EPAD") (pintype "power_in"))
      (node (ref "U401") (pin "VCC-") (pinfunction "GND_VCC-") (pintype "bidirectional"))
      (node (ref "X101") (pin "2") (pinfunction "SHIELD_2") (pintype "power_in"))
      (node (ref "X101") (pin "4") (pinfunction "SHIELD_4") (pintype "power_in"))
    )
    (net (code "8") (name "NRESET") (class "Default")
      (node (ref "J1") (pin "!RESET") (pinfunction "~{RESET}_!RESET") (pintype "passive"))
      (node (ref "U100") (pin "4") (pinfunction "NRST_4") (pintype "bidirectional"))
    )
    (net (code "9") (name "Net-(C306-Pad1)") (class "Default")
      (node (ref "C306") (pin "1") (pinfunction "1_1") (pintype "passive"))
      (node (ref "R308") (pin "1") (pinfunction "1_1") (pintype "passive"))
      (node (ref "R309") (pin "2") (pinfunction "2_2") (pintype "passive"))
      (node (ref "U301") (pin "IN+") (pinfunction "IN+_IN+") (pintype "bidirectional"))
    )
    (net (code "10") (name "Net-(C307-Pad1)") (class "Default")
      (node (ref "C307") (pin "1") (pinfunction "1_1") (pintype "passive"))
      (node (ref "R312") (pin "1") (pinfunction "1_1") (pintype "passive"))
      (node (ref "R313") (pin "2") (pinfunction "2_2") (pintype "passive"))
      (node (ref "U301") (pin "IN-") (pinfunction "IN-_IN-") (pintype "bidirectional"))
    )
    (net (code "11") (name "Net-(C307-Pad2)") (class "Default")
      (node (ref "C307") (pin "2") (pinfunction "2_2") (pintype "passive"))
      (node (ref "R313") (pin "1") (pinfunction "1_1") (pintype "passive"))
      (node (ref "R314") (pin "2") (pinfunction "2_2") (pintype "passive"))
      (node (ref "U301") (pin "OUT") (pinfunction "OUT_OUT") (pintype "bidirectional"))
    )
    (net (code "12") (name "Net-(C406-Pad2)") (class "Default")
      (node (ref "C406") (pin "2") (pinfunction "2_2") (pintype "passive"))
      (node (ref "R407") (pin "2") (pinfunction "2_2") (pintype "passive"))
    )
    (net (code "13") (name "Net-(C408-Pad1)") (class "Default")
      (node (ref "C408") (pin "1") (pinfunction "1_1") (pintype "passive"))
      (node (ref "R413") (pin "1") (pinfunction "1_1") (pintype "passive"))
      (node (ref "R414") (pin "2") (pinfunction "2_2") (pintype "passive"))
      (node (ref "U401") (pin "IN+") (pinfunction "IN+_IN+") (pintype "bidirectional"))
    )
    (net (code "14") (name "Net-(C411-Pad1)") (class "Default")
      (node (ref "C411") (pin "1") (pinfunction "1_1") (pintype "passive"))
      (node (ref "R417") (pin "1") (pinfunction "1_1") (pintype "passive"))
      (node (ref "R418") (pin "2") (pinfunction "2_2") (pintype "passive"))
      (node (ref "U401") (pin "IN-") (pinfunction "IN-_IN-") (pintype "bidirectional"))
    )
    (net (code "15") (name "Net-(C411-Pad2)") (class "Default")
      (node (ref "C411") (pin "2") (pinfunction "2_2") (pintype "passive"))
      (node (ref "R418") (pin "1") (pinfunction "1_1") (pintype "passive"))
      (node (ref "R419") (pin "2") (pinfunction "2_2") (pintype "passive"))
      (node (ref "U401") (pin "OUT") (pinfunction "OUT_OUT") (pintype "bidirectional"))
    )
    (net (code "16") (name "Net-(D201-PadA)") (class "Default")
      (node (ref "D201") (pin "A") (pinfunction "A_A") (pintype "passive"))
      (node (ref "R208") (pin "1") (pinfunction "1_1") (pintype "passive"))
    )
    (net (code "17") (name "Net-(D202-PadA)") (class "Default")
      (node (ref "D202") (pin "A") (pinfunction "A_A") (pintype "passive"))
      (node (ref "R209") (pin "1") (pinfunction "1_1") (pintype "passive"))
    )
    (net (code "18") (name "Net-(LED+-PadA)") (class "Default")
      (node (ref "LED+") (pin "A") (pinfunction "A_A") (pintype "passive"))
      (node (ref "R411") (pin "1") (pinfunction "1_1") (pintype "passive"))
    )
    (net (code "19") (name "Net-(LED--PadA)") (class "Default")
      (node (ref "LED-") (pin "A") (pinfunction "A_A") (pintype "passive"))
      (node (ref "R412") (pin "2") (pinfunction "2_2") (pintype "passive"))
    )
    (net (code "20") (name "Net-(LEDU-PadA)") (class "Default")
      (node (ref "LEDU") (pin "A") (pinfunction "A_A") (pintype "passive"))
      (node (ref "R305") (pin "1") (pinfunction "1_1") (pintype "passive"))
    )
    (net (code "21") (name "Net-(LEDV-PadA)") (class "Default")
      (node (ref "LEDV") (pin "A") (pinfunction "A_A") (pintype "passive"))
      (node (ref "R306") (pin "1") (pinfunction "1_1") (pintype "passive"))
    )
    (net (code "22") (name "Net-(LEDW-PadA)") (class "Default")
      (node (ref "LEDW") (pin "A") (pinfunction "A_A") (pintype "passive"))
      (node (ref "R307") (pin "1") (pinfunction "1_1") (pintype "passive"))
    )
    (net (code "23") (name "Net-(U100-PB8-BOOT0)") (class "Default")
      (node (ref "R101") (pin "2") (pinfunction "2_2") (pintype "passive"))
      (node (ref "TP101") (pin "1") (pinfunction "1_1") (pintype "passive"))
      (node (ref "U100") (pin "31") (pinfunction "PB8-BOOT0_31") (pintype "bidirectional"))
    )
    (net (code "24") (name "Net-(U100-PF0-OSC_IN)") (class "Default")
      (node (ref "C105") (pin "1") (pinfunction "1_1") (pintype "passive"))
      (node (ref "U100") (pin "2") (pinfunction "PF0-OSC_IN_2") (pintype "bidirectional"))
      (node (ref "X101") (pin "1") (pinfunction "1_1") (pintype "passive"))
    )
    (net (code "25") (name "Net-(U100-PF1-OSC_OUT)") (class "Default")
      (node (ref "C104") (pin "1") (pinfunction "1_1") (pintype "passive"))
      (node (ref "U100") (pin "3") (pinfunction "PF1-OSC_OUT_3") (pintype "bidirectional"))
      (node (ref "X101") (pin "3") (pinfunction "2_3") (pintype "passive"))
    )
    (net (code "26") (name "Net-(U200-EN)") (class "Default")
      (node (ref "R202") (pin "1") (pinfunction "1_1") (pintype "passive"))
      (node (ref "R203") (pin "2") (pinfunction "2_2") (pintype "passive"))
      (node (ref "TP201") (pin "1") (pinfunction "1_1") (pintype "passive"))
      (node (ref "U200") (pin "1") (pinfunction "PS/SYNC_1") (pintype "input"))
      (node (ref "U200") (pin "14") (pinfunction "EN_14") (pintype "input"))
    )
    (net (code "27") (name "Net-(U200-FB)") (class "Default")
      (node (ref "R205") (pin "1") (pinfunction "1_1") (pintype "passive"))
      (node (ref "R206") (pin "2") (pinfunction "2_2") (pintype "passive"))
      (node (ref "U200") (pin "5") (pinfunction "FB_5") (pintype "passive"))
    )
    (net (code "28") (name "Net-(U200-FB2)") (class "Default")
      (node (ref "TP204") (pin "1") (pinfunction "1_1") (pintype "passive"))
      (node (ref "U200") (pin "6") (pinfunction "FB2_6") (pintype "passive"))
    )
    (net (code "29") (name "Net-(U200-L1)") (class "Default")
      (node (ref "L201") (pin "1") (pinfunction "1_1") (pintype "passive"))
      (node (ref "U200") (pin "11") (pinfunction "L1_11") (pintype "passive"))
    )
    (net (code "30") (name "Net-(U200-L2)") (class "Default")
      (node (ref "L201") (pin "2") (pinfunction "2_2") (pintype "passive"))
      (node (ref "U200") (pin "9") (pinfunction "L2_9") (pintype "passive"))
    )
    (net (code "31") (name "Net-(U200-PG)") (class "Default")
      (node (ref "R207") (pin "1") (pinfunction "1_1") (pintype "passive"))
      (node (ref "TP203") (pin "1") (pinfunction "1_1") (pintype "passive"))
      (node (ref "U200") (pin "2") (pinfunction "PG_2") (pintype "open_collector"))
    )
    (net (code "32") (name "Net-(U200-VAUX)") (class "Default")
      (node (ref "C204") (pin "1") (pinfunction "1_1") (pintype "passive"))
      (node (ref "U200") (pin "3") (pinfunction "VAUX_3") (pintype "output"))
    )
    (net (code "33") (name "Net-(U200-VIN)") (class "Default")
      (node (ref "C201") (pin "1") (pinfunction "1_1") (pintype "passive"))
      (node (ref "C202") (pin "1") (pinfunction "1_1") (pintype "passive"))
      (node (ref "C203") (pin "1") (pinfunction "1_1") (pintype "passive"))
      (node (ref "R201") (pin "1") (pinfunction "1_1") (pintype "passive"))
      (node (ref "R202") (pin "2") (pinfunction "2_2") (pintype "passive"))
      (node (ref "U200") (pin "12-13") (pinfunction "VIN_12-13") (pintype "power_in"))
    )
    (net (code "34") (name "Net-(U200-VSEL)") (class "Default")
      (node (ref "R204") (pin "2") (pinfunction "2_2") (pintype "passive"))
      (node (ref "TP202") (pin "1") (pinfunction "1_1") (pintype "passive"))
      (node (ref "U200") (pin "15") (pinfunction "VSEL_15") (pintype "input"))
    )
    (net (code "35") (name "Net-(U300-OUTU)") (class "Default")
      (node (ref "JP301") (pin "1") (pinfunction "1_1") (pintype "passive"))
      (node (ref "R305") (pin "2") (pinfunction "2_2") (pintype "passive"))
      (node (ref "U300") (pin "3") (pinfunction "OUTU_3") (pintype "output"))
    )
    (net (code "36") (name "Net-(U300-OUTV)") (class "Default")
      (node (ref "JP301") (pin "2") (pinfunction "2_2") (pintype "passive"))
      (node (ref "R306") (pin "2") (pinfunction "2_2") (pintype "passive"))
      (node (ref "U300") (pin "8") (pinfunction "OUTV_8") (pintype "output"))
    )
    (net (code "37") (name "Net-(U300-OUTW)") (class "Default")
      (node (ref "JP301") (pin "3") (pinfunction "3_3") (pintype "passive"))
      (node (ref "R307") (pin "2") (pinfunction "2_2") (pintype "passive"))
      (node (ref "U300") (pin "10") (pinfunction "OUTW_10") (pintype "output"))
    )
    (net (code "38") (name "Net-(U300-SENSEU)") (class "Default")
      (node (ref "R309") (pin "1") (pinfunction "1_1") (pintype "passive"))
      (node (ref "R310") (pin "2") (pinfunction "2_2") (pintype "passive"))
      (node (ref "R311") (pin "2") (pinfunction "2_2") (pintype "passive"))
      (node (ref "U300") (pin "4") (pinfunction "SENSEU_4") (pintype "output"))
      (node (ref "U300") (pin "9") (pinfunction "SENSEVW_9") (pintype "output"))
    )
    (net (code "39") (name "Net-(U300-VS)") (class "Default")
      (node (ref "C301") (pin "1") (pinfunction "1_1") (pintype "passive"))
      (node (ref "C302") (pin "1") (pinfunction "1_1") (pintype "passive"))
      (node (ref "C303") (pin "1") (pinfunction "1_1") (pintype "passive"))
      (node (ref "R303") (pin "1") (pinfunction "1_1") (pintype "passive"))
      (node (ref "R304") (pin "1") (pinfunction "1_1") (pintype "passive"))
      (node (ref "U300") (pin "6") (pinfunction "VS_6") (pintype "power_in"))
    )
    (net (code "40") (name "Net-(U302-A)") (class "Default")
      (node (ref "JP302") (pin "1") (pinfunction "1_1") (pintype "passive"))
      (node (ref "U302") (pin "7") (pinfunction "A_7") (pintype "output"))
    )
    (net (code "41") (name "Net-(U302-B)") (class "Default")
      (node (ref "JP302") (pin "2") (pinfunction "2_2") (pintype "passive"))
      (node (ref "U302") (pin "6") (pinfunction "B_6") (pintype "output"))
    )
    (net (code "42") (name "Net-(U302-MOSI)") (class "Default")
      (node (ref "R315") (pin "2") (pinfunction "2_2") (pintype "passive"))
      (node (ref "U302") (pin "4") (pinfunction "MOSI_4") (pintype "input"))
    )
    (net (code "43") (name "Net-(U400-OUTA1)") (class "Default")
      (node (ref "JP401") (pin "1") (pinfunction "1_1") (pintype "passive"))
      (node (ref "LED-") (pin "C") (pinfunction "C_C") (pintype "passive"))
      (node (ref "R411") (pin "2") (pinfunction "2_2") (pintype "passive"))
      (node (ref "U400") (pin "10") (pinfunction "OUTB1_10") (pintype "output"))
      (node (ref "U400") (pin "3") (pinfunction "OUTA1_3") (pintype "output"))
    )
    (net (code "44") (name "Net-(U400-OUTA2)") (class "Default")
      (node (ref "JP401") (pin "2") (pinfunction "2_2") (pintype "passive"))
      (node (ref "LED+") (pin "C") (pinfunction "C_C") (pintype "passive"))
      (node (ref "R412") (pin "1") (pinfunction "1_1") (pintype "passive"))
      (node (ref "U400") (pin "5") (pinfunction "OUTA2_5") (pintype "output"))
      (node (ref "U400") (pin "8") (pinfunction "OUTB2_8") (pintype "output"))
    )
    (net (code "45") (name "Net-(U400-PH)") (class "Default")
      (node (ref "R405") (pin "1") (pinfunction "1_1") (pintype "passive"))
      (node (ref "U400") (pin "1") (pinfunction "PH_1") (pintype "input"))
    )
    (net (code "46") (name "Net-(U400-PWM)") (class "Default")
      (node (ref "R406") (pin "1") (pinfunction "1_1") (pintype "passive"))
      (node (ref "U400") (pin "2") (pinfunction "PWM_2") (pintype "input"))
    )
    (net (code "47") (name "Net-(U400-REF)") (class "Default")
      (node (ref "C407") (pin "2") (pinfunction "2_2") (pintype "passive"))
      (node (ref "R409") (pin "2") (pinfunction "2_2") (pintype "passive"))
      (node (ref "R410") (pin "1") (pinfunction "1_1") (pintype "passive"))
      (node (ref "U400") (pin "11") (pinfunction "REF_11") (pintype "passive"))
    )
    (net (code "48") (name "Net-(U400-SENSEA)") (class "Default")
      (node (ref "R414") (pin "1") (pinfunction "1_1") (pintype "passive"))
      (node (ref "R415") (pin "1") (pinfunction "1_1") (pintype "passive"))
      (node (ref "R416") (pin "1") (pinfunction "1_1") (pintype "passive"))
      (node (ref "U400") (pin "4") (pinfunction "SENSEA_4") (pintype "output"))
      (node (ref "U400") (pin "9") (pinfunction "SENSEB_9") (pintype "output"))
    )
    (net (code "49") (name "Net-(U400-TOFF)") (class "Default")
      (node (ref "R407") (pin "1") (pinfunction "1_1") (pintype "passive"))
      (node (ref "R408") (pin "1") (pinfunction "1_1") (pintype "passive"))
      (node (ref "U400") (pin "12") (pinfunction "TOFF_12") (pintype "passive"))
    )
    (net (code "50") (name "Net-(U400-VS)") (class "Default")
      (node (ref "C401") (pin "1") (pinfunction "1_1") (pintype "passive"))
      (node (ref "C402") (pin "1") (pinfunction "1_1") (pintype "passive"))
      (node (ref "C403") (pin "1") (pinfunction "1_1") (pintype "passive"))
      (node (ref "R403") (pin "1") (pinfunction "1_1") (pintype "passive"))
      (node (ref "R404") (pin "1") (pinfunction "1_1") (pintype "passive"))
      (node (ref "U400") (pin "6") (pinfunction "VS_6") (pintype "power_in"))
    )
    (net (code "51") (name "PA0{slash}CURR_FDB_BLDC") (class "Default")
      (node (ref "R314") (pin "1") (pinfunction "1_1") (pintype "passive"))
      (node (ref "U100") (pin "6") (pinfunction "PA0_6") (pintype "bidirectional"))
    )
    (net (code "52") (name "PA1{slash}CURR_FDB_MAG") (class "Default")
      (node (ref "R419") (pin "1") (pinfunction "1_1") (pintype "passive"))
      (node (ref "U100") (pin "7") (pinfunction "PA1_7") (pintype "bidirectional"))
    )
    (net (code "53") (name "PA2{slash}USART2_TX") (class "Default")
      (node (ref "JP102") (pin "P$2") (pinfunction "TXO_P$2") (pintype "passive"))
      (node (ref "U100") (pin "8") (pinfunction "PA2_8") (pintype "bidirectional"))
    )
    (net (code "54") (name "PA3{slash}USART2_RX") (class "Default")
      (node (ref "JP102") (pin "P$3") (pinfunction "RXI_P$3") (pintype "passive"))
      (node (ref "U100") (pin "9") (pinfunction "PA3_9") (pintype "bidirectional"))
    )
    (net (code "55") (name "PA4{slash}FAULT_BLDC") (class "Default")
      (node (ref "C305") (pin "2") (pinfunction "2_2") (pintype "passive"))
      (node (ref "R302") (pin "1") (pinfunction "1_1") (pintype "passive"))
      (node (ref "U100") (pin "10") (pinfunction "PA4_10") (pintype "bidirectional"))
      (node (ref "U300") (pin "13") (pinfunction "EN/FAULT_13") (pintype "bidirectional"))
    )
    (net (code "56") (name "PA5{slash}SPI1_SCK") (class "Default")
      (node (ref "U100") (pin "11") (pinfunction "PA5_11") (pintype "bidirectional"))
      (node (ref "U302") (pin "2") (pinfunction "SCLK_2") (pintype "input"))
    )
    (net (code "57") (name "PA6{slash}CAN_LSTN") (class "Default")
      (node (ref "U100") (pin "12") (pinfunction "PA6_12") (pintype "bidirectional"))
      (node (ref "U101") (pin "8") (pinfunction "S_8") (pintype "input"))
    )
    (net (code "58") (name "PA7{slash}INUL") (class "Default")
      (node (ref "U100") (pin "13") (pinfunction "PA7_13") (pintype "bidirectional"))
      (node (ref "U300") (pin "1") (pinfunction "INUL_1") (pintype "input"))
    )
    (net (code "59") (name "PA8{slash}INUH{slash}PWM_MAG") (class "Default")
      (node (ref "R406") (pin "2") (pinfunction "2_2") (pintype "passive"))
      (node (ref "U100") (pin "18") (pinfunction "PA8_18") (pintype "bidirectional"))
      (node (ref "U300") (pin "2") (pinfunction "INUH_2") (pintype "input"))
    )
    (net (code "60") (name "PA9{slash}INVH{slash}DIR_MAG") (class "Default")
      (node (ref "R405") (pin "2") (pinfunction "2_2") (pintype "passive"))
      (node (ref "U100") (pin "19") (pinfunction "PA9_19") (pintype "bidirectional"))
      (node (ref "U300") (pin "16") (pinfunction "INVH_16") (pintype "input"))
    )
    (net (code "61") (name "PA10{slash}INWH") (class "Default")
      (node (ref "U100") (pin "20") (pinfunction "PA10_20") (pintype "bidirectional"))
      (node (ref "U300") (pin "12") (pinfunction "INWH_12") (pintype "input"))
    )
    (net (code "62") (name "PA15{slash}SPI1_NSS") (class "Default")
      (node (ref "U100") (pin "25") (pinfunction "PA15_25") (pintype "bidirectional"))
      (node (ref "U302") (pin "1") (pinfunction "CSN_1") (pintype "input"))
    )
    (net (code "63") (name "PB0{slash}INVL") (class "Default")
      (node (ref "U100") (pin "14") (pinfunction "PB0_14") (pintype "bidirectional"))
      (node (ref "U300") (pin "15") (pinfunction "INVL_15") (pintype "input"))
    )
    (net (code "64") (name "PB1{slash}INWL") (class "Default")
      (node (ref "U100") (pin "15") (pinfunction "PB1_15") (pintype "bidirectional"))
      (node (ref "U300") (pin "11") (pinfunction "INWL_11") (pintype "input"))
    )
    (net (code "65") (name "PB3{slash}EN_MAG") (class "Default")
      (node (ref "R402") (pin "2") (pinfunction "2_2") (pintype "passive"))
      (node (ref "U100") (pin "26") (pinfunction "PB3_26") (pintype "bidirectional"))
    )
    (net (code "66") (name "PB4{slash}SPI1_MISO") (class "Default")
      (node (ref "U100") (pin "27") (pinfunction "PB4_27") (pintype "bidirectional"))
      (node (ref "U302") (pin "3") (pinfunction "MISO_3") (pintype "output"))
    )
    (net (code "67") (name "PB5") (class "Default")
      (node (ref "U100") (pin "28") (pinfunction "PB5_28") (pintype "bidirectional"))
    )
    (net (code "68") (name "PB6{slash}EN_BLDC") (class "Default")
      (node (ref "R302") (pin "2") (pinfunction "2_2") (pintype "passive"))
      (node (ref "U100") (pin "29") (pinfunction "PB6_29") (pintype "bidirectional"))
    )
    (net (code "69") (name "PB7{slash}FAULT_MAG") (class "Default")
      (node (ref "C405") (pin "2") (pinfunction "2_2") (pintype "passive"))
      (node (ref "R402") (pin "1") (pinfunction "1_1") (pintype "passive"))
      (node (ref "U100") (pin "30") (pinfunction "PB7_30") (pintype "bidirectional"))
      (node (ref "U400") (pin "13") (pinfunction "EN/FAULT_13") (pintype "bidirectional"))
    )
    (net (code "70") (name "STBY{slash}RESET_BLDC") (class "Default")
      (node (ref "C304") (pin "2") (pinfunction "2_2") (pintype "passive"))
      (node (ref "R301") (pin "1") (pinfunction "1_1") (pintype "passive"))
      (node (ref "U300") (pin "14") (pinfunction "STBY/RESET_14") (pintype "input"))
    )
    (net (code "71") (name "STBY{slash}RESET_MAG") (class "Default")
      (node (ref "C404") (pin "2") (pinfunction "2_2") (pintype "passive"))
      (node (ref "R401") (pin "1") (pinfunction "1_1") (pintype "passive"))
      (node (ref "U400") (pin "14") (pinfunction "STBY/RESET_14") (pintype "bidirectional"))
    )
    (net (code "72") (name "SWCLK") (class "Default")
      (node (ref "J1") (pin "SWDCLK") (pinfunction "SWDCLK/TCK_SWDCLK") (pintype "passive"))
      (node (ref "U100") (pin "24") (pinfunction "PA14-SWCLK_24") (pintype "bidirectional"))
    )
    (net (code "73") (name "SWDIO") (class "Default")
      (node (ref "J1") (pin "SWDIO") (pinfunction "SWDIO/TMS_SWDIO") (pintype "passive"))
      (node (ref "U100") (pin "23") (pinfunction "PA13-SWDIO_23") (pintype "bidirectional"))
    )
    (net (code "74") (name "V_BATT") (class "Default")
      (node (ref "JP101") (pin "1") (pinfunction "1_1") (pintype "passive"))
      (node (ref "R201") (pin "2") (pinfunction "2_2") (pintype "passive"))
      (node (ref "R208") (pin "2") (pinfunction "2_2") (pintype "passive"))
      (node (ref "R303") (pin "2") (pinfunction "2_2") (pintype "passive"))
      (node (ref "R403") (pin "2") (pinfunction "2_2") (pintype "passive"))
    )
    (net (code "75") (name "unconnected-(J1-GND-PadGND@2)") (class "Default")
      (node (ref "J1") (pin "GND@2") (pinfunction "GND_GND@2") (pintype "passive"))
    )
    (net (code "76") (name "unconnected-(J1-NC{slash}TDI-PadNC)") (class "Default")
      (node (ref "J1") (pin "NC") (pinfunction "NC/TDI_NC") (pintype "passive"))
    )
    (net (code "77") (name "unconnected-(J1-PadGND)") (class "Default")
      (node (ref "J1") (pin "GND") (pinfunction "GND_GND") (pintype "passive"))
    )
    (net (code "78") (name "unconnected-(J1-PadGNDDET)") (class "Default")
      (node (ref "J1") (pin "GNDDET") (pinfunction "GNDDET_GNDDET") (pintype "passive"))
    )
    (net (code "79") (name "unconnected-(J1-PadVTREF)") (class "Default")
      (node (ref "J1") (pin "VTREF") (pinfunction "VTREF_VTREF") (pintype "passive"))
    )
    (net (code "80") (name "unconnected-(J1-SWO{slash}TDO-PadSWO)") (class "Default")
      (node (ref "J1") (pin "SWO") (pinfunction "SWO/TDO_SWO") (pintype "passive"))
    )
    (net (code "81") (name "unconnected-(JP102-CTS-PadP$5)") (class "Default")
      (node (ref "JP102") (pin "P$5") (pinfunction "CTS_P$5") (pintype "passive"))
    )
    (net (code "82") (name "unconnected-(JP102-DTR-PadP$1)") (class "Default")
      (node (ref "JP102") (pin "P$1") (pinfunction "DTR_P$1") (pintype "passive"))
    )
    (net (code "83") (name "unconnected-(JP102-VCC-PadP$4)") (class "Default")
      (node (ref "JP102") (pin "P$4") (pinfunction "VCC_P$4") (pintype "passive"))
    )
    (net (code "84") (name "unconnected-(U302-I{slash}PWM-Pad14)") (class "Default")
      (node (ref "U302") (pin "14") (pinfunction "I/PWM_14") (pintype "output"))
    )
    (net (code "85") (name "unconnected-(U302-U-Pad10)") (class "Default")
      (node (ref "U302") (pin "10") (pinfunction "U_10") (pintype "output"))
    )
    (net (code "86") (name "unconnected-(U302-V-Pad9)") (class "Default")
      (node (ref "U302") (pin "9") (pinfunction "V_9") (pintype "output"))
    )
    (net (code "87") (name "unconnected-(U302-W{slash}PWM-Pad8)") (class "Default")
      (node (ref "U302") (pin "8") (pinfunction "W/PWM_8") (pintype "output"))
    )
  )
)
